# activeElectrode_adapter.net
KiCad netlist of a schematic drawn in EAGLE
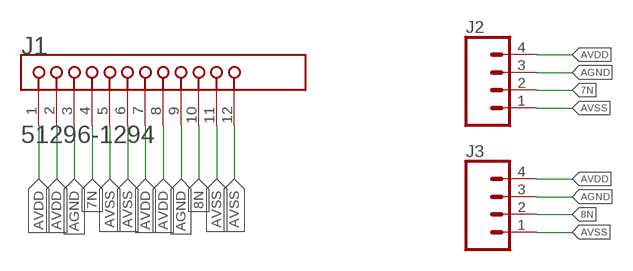
[diagram p0: schematic, sheet 1]

(export (version "E")
  (design (tool "Eeschema 10.0.6"))
  (components
    (comp (ref "J1")
      (value "MOLEX_51296-1294_FLEX")
      (footprint "eagle-import:MOLEX_51296-1294_FLEX")
      (libsource (lib "eagle-import") (part "MOLEX_51296-1294_FLEX"))
    )
    (comp (ref "J2")
      (value "CONN_04AE_4PIN")
      (footprint "eagle-import:AE-4-PTH")
      (libsource (lib "eagle-import") (part "CONN_04AE_4PIN"))
    )
    (comp (ref "J3")
      (value "CONN_04AE_4PIN")
      (footprint "eagle-import:AE-4-PTH")
      (libsource (lib "eagle-import") (part "CONN_04AE_4PIN"))
    )
  )
  (nets
    (net (code "1") (name "7N") (class "Default")
      (node (ref "J1") (pin "4") (pinfunction "4_4") (pintype "passive"))
      (node (ref "J2") (pin "2") (pinfunction "2_2") (pintype "passive"))
    )
    (net (code "2") (name "8N") (class "Default")
      (node (ref "J1") (pin "10") (pinfunction "10_10") (pintype "passive"))
      (node (ref "J3") (pin "2") (pinfunction "2_2") (pintype "passive"))
    )
    (net (code "3") (name "AGND") (class "Default")
      (node (ref "J1") (pin "3") (pinfunction "3_3") (pintype "passive"))
      (node (ref "J1") (pin "9") (pinfunction "9_9") (pintype "passive"))
      (node (ref "J2") (pin "3") (pinfunction "3_3") (pintype "passive"))
      (node (ref "J3") (pin "3") (pinfunction "3_3") (pintype "passive"))
    )
    (net (code "4") (name "AVDD") (class "Default")
      (node (ref "J1") (pin "1") (pinfunction "1_1") (pintype "passive"))
      (node (ref "J1") (pin "2") (pinfunction "2_2") (pintype "passive"))
      (node (ref "J1") (pin "7") (pinfunction "7_7") (pintype "passive"))
      (node (ref "J1") (pin "8") (pinfunction "8_8") (pintype "passive"))
      (node (ref "J2") (pin "4") (pinfunction "4_4") (pintype "passive"))
      (node (ref "J3") (pin "4") (pinfunction "4_4") (pintype "passive"))
    )
    (net (code "5") (name "AVSS") (class "Default")
      (node (ref "J1") (pin "11") (pinfunction "11_11") (pintype "passive"))
      (node (ref "J1") (pin "12") (pinfunction "12_12") (pintype "passive"))
      (node (ref "J1") (pin "5") (pinfunction "5_5") (pintype "passive"))
      (node (ref "J1") (pin "6") (pinfunction "6_6") (pintype "passive"))
      (node (ref "J2") (pin "1") (pinfunction "1_1") (pintype "passive"))
      (node (ref "J3") (pin "1") (pinfunction "1_1") (pintype "passive"))
    )
  )
)
